# schematic.net
KiCad netlist of a schematic drawn in Altium Designer
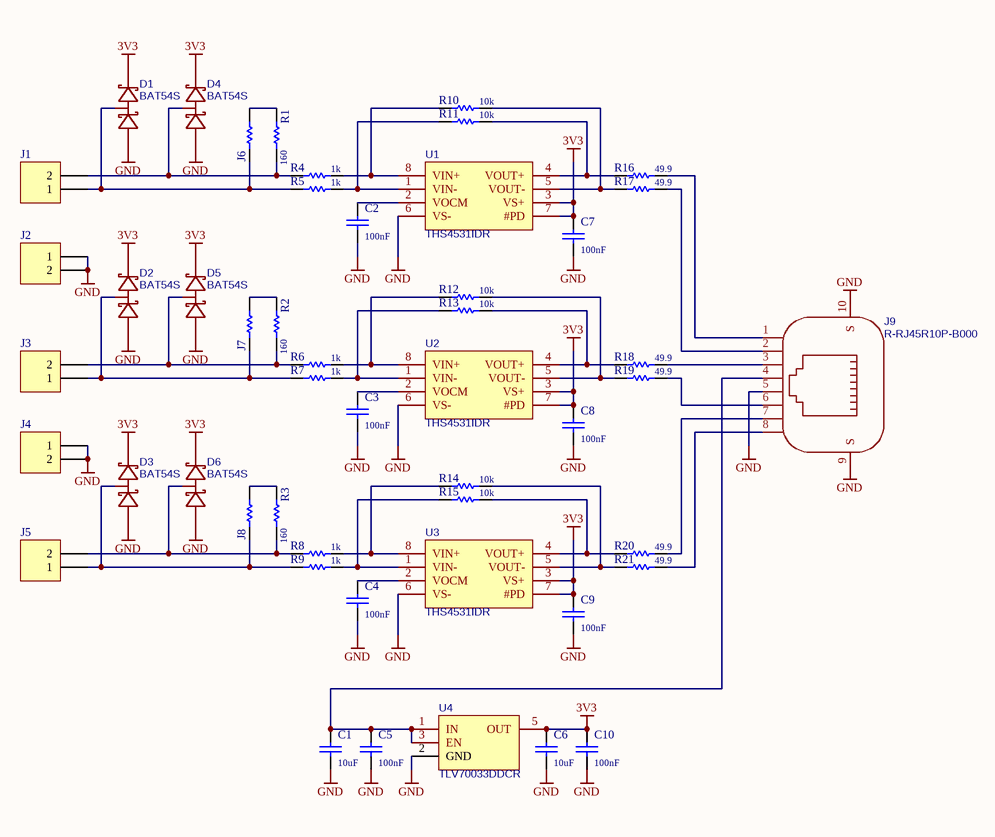
[diagram p0: schematic.SchDoc]

(export (version "E")
  (design (tool "Eeschema 10.0.6"))
  (components
    (comp (ref "C1")
      (value "10uF")
      (footprint "C0805")
      (description "10uf 50V 1206")
      (libsource (lib "Miscellaneous Devices") (part "CAP"))
    )
    (comp (ref "C2")
      (value "100nF")
      (footprint "C0603")
      (description "100nF 0603")
      (libsource (lib "Miscellaneous Devices") (part "CAP"))
    )
    (comp (ref "C3")
      (value "100nF")
      (footprint "C0603")
      (description "100nF 0603")
      (libsource (lib "Miscellaneous Devices") (part "CAP"))
    )
    (comp (ref "C4")
      (value "100nF")
      (footprint "C0603")
      (description "100nF 0603")
      (libsource (lib "Miscellaneous Devices") (part "CAP"))
    )
    (comp (ref "C5")
      (value "100nF")
      (footprint "C0603")
      (description "100nF 0603")
      (libsource (lib "Miscellaneous Devices") (part "CAP"))
    )
    (comp (ref "C6")
      (value "10uF")
      (footprint "C0805")
      (description "10uf 50V 1206")
      (libsource (lib "Miscellaneous Devices") (part "CAP"))
    )
    (comp (ref "C7")
      (value "100nF")
      (footprint "C0603")
      (description "100nF 0603")
      (libsource (lib "Miscellaneous Devices") (part "CAP"))
    )
    (comp (ref "C8")
      (value "100nF")
      (footprint "C0603")
      (description "100nF 0603")
      (libsource (lib "Miscellaneous Devices") (part "CAP"))
    )
    (comp (ref "C9")
      (value "100nF")
      (footprint "C0603")
      (description "100nF 0603")
      (libsource (lib "Miscellaneous Devices") (part "CAP"))
    )
    (comp (ref "C10")
      (value "100nF")
      (footprint "C0603")
      (description "100nF 0603")
      (libsource (lib "Miscellaneous Devices") (part "CAP"))
    )
    (comp (ref "D1")
      (value "BAT54S")
      (footprint "SOT-23")
      (libsource (lib "Schlib1") (part "BAT54S_C916425"))
    )
    (comp (ref "D2")
      (value "BAT54S")
      (footprint "SOT-23")
      (libsource (lib "Schlib1") (part "BAT54S_C916425"))
    )
    (comp (ref "D3")
      (value "BAT54S")
      (footprint "SOT-23")
      (libsource (lib "Schlib1") (part "BAT54S_C916425"))
    )
    (comp (ref "D4")
      (value "BAT54S")
      (footprint "SOT-23")
      (libsource (lib "Schlib1") (part "BAT54S_C916425"))
    )
    (comp (ref "D5")
      (value "BAT54S")
      (footprint "SOT-23")
      (libsource (lib "Schlib1") (part "BAT54S_C916425"))
    )
    (comp (ref "D6")
      (value "BAT54S")
      (footprint "SOT-23")
      (libsource (lib "Schlib1") (part "BAT54S_C916425"))
    )
    (comp (ref "J1")
      (value "DG308-2.54-02P-14-00A(H)")
      (footprint "CONN_DG308-2.54-2P")
      (libsource (lib "Miscellaneous Devices") (part "CONN MOLEX HDR-M 1x4"))
    )
    (comp (ref "J2")
      (value "DG308-2.54-02P-14-00A(H)")
      (footprint "CONN_DG308-2.54-2P")
      (libsource (lib "") (part "CONN MOLEX HDR-M 1x4_1"))
    )
    (comp (ref "J3")
      (value "DG308-2.54-02P-14-00A(H)")
      (footprint "CONN_DG308-2.54-2P")
      (libsource (lib "Miscellaneous Devices") (part "CONN MOLEX HDR-M 1x4"))
    )
    (comp (ref "J4")
      (value "DG308-2.54-02P-14-00A(H)")
      (footprint "CONN_DG308-2.54-2P")
      (libsource (lib "") (part "CONN MOLEX HDR-M 1x4_1"))
    )
    (comp (ref "J5")
      (value "DG308-2.54-02P-14-00A(H)")
      (footprint "CONN_DG308-2.54-2P")
      (libsource (lib "Miscellaneous Devices") (part "CONN MOLEX HDR-M 1x4"))
    )
    (comp (ref "J6")
      (value "undef")
      (footprint "R0603")
      (libsource (lib "Miscellaneous Devices") (part "RES"))
    )
    (comp (ref "J7")
      (value "undef")
      (footprint "R0603")
      (libsource (lib "Miscellaneous Devices") (part "RES"))
    )
    (comp (ref "J8")
      (value "undef")
      (footprint "R0603")
      (libsource (lib "Miscellaneous Devices") (part "RES"))
    )
    (comp (ref "J9")
      (value "R-RJ45R10P-B000")
      (footprint "RJ45-TH_R-RJ45R10P-B000")
      (libsource (lib "altium-import") (part "root_3_R-RJ45R10P-B000_"))
    )
    (comp (ref "R1")
      (value "160")
      (footprint "R0603")
      (description "160R 0603")
      (libsource (lib "Miscellaneous Devices") (part "RES"))
    )
    (comp (ref "R2")
      (value "160")
      (footprint "R0603")
      (description "160R 0603")
      (libsource (lib "Miscellaneous Devices") (part "RES"))
    )
    (comp (ref "R3")
      (value "160")
      (footprint "R0603")
      (description "160R 0603")
      (libsource (lib "Miscellaneous Devices") (part "RES"))
    )
    (comp (ref "R4")
      (value "1k")
      (footprint "R0603")
      (description "1k 0603")
      (libsource (lib "Miscellaneous Devices") (part "RES"))
    )
    (comp (ref "R5")
      (value "1k")
      (footprint "R0603")
      (description "1k 0603")
      (libsource (lib "Miscellaneous Devices") (part "RES"))
    )
    (comp (ref "R6")
      (value "1k")
      (footprint "R0603")
      (description "1k 0603")
      (libsource (lib "Miscellaneous Devices") (part "RES"))
    )
    (comp (ref "R7")
      (value "1k")
      (footprint "R0603")
      (description "1k 0603")
      (libsource (lib "Miscellaneous Devices") (part "RES"))
    )
    (comp (ref "R8")
      (value "1k")
      (footprint "R0603")
      (description "1k 0603")
      (libsource (lib "Miscellaneous Devices") (part "RES"))
    )
    (comp (ref "R9")
      (value "1k")
      (footprint "R0603")
      (description "1k 0603")
      (libsource (lib "Miscellaneous Devices") (part "RES"))
    )
    (comp (ref "R10")
      (value "10k")
      (footprint "R0603")
      (description "10k 0603")
      (libsource (lib "Miscellaneous Devices") (part "RES"))
    )
    (comp (ref "R11")
      (value "10k")
      (footprint "R0603")
      (description "10k 0603")
      (libsource (lib "Miscellaneous Devices") (part "RES"))
    )
    (comp (ref "R12")
      (value "10k")
      (footprint "R0603")
      (description "10k 0603")
      (libsource (lib "Miscellaneous Devices") (part "RES"))
    )
    (comp (ref "R13")
      (value "10k")
      (footprint "R0603")
      (description "10k 0603")
      (libsource (lib "Miscellaneous Devices") (part "RES"))
    )
    (comp (ref "R14")
      (value "10k")
      (footprint "R0603")
      (description "10k 0603")
      (libsource (lib "Miscellaneous Devices") (part "RES"))
    )
    (comp (ref "R15")
      (value "10k")
      (footprint "R0603")
      (description "10k 0603")
      (libsource (lib "Miscellaneous Devices") (part "RES"))
    )
    (comp (ref "R16")
      (value "49.9")
      (footprint "R0603")
      (description "49.9R")
      (libsource (lib "Miscellaneous Devices") (part "RES"))
    )
    (comp (ref "R17")
      (value "49.9")
      (footprint "R0603")
      (description "49.9R")
      (libsource (lib "Miscellaneous Devices") (part "RES"))
    )
    (comp (ref "R18")
      (value "49.9")
      (footprint "R0603")
      (description "49.9R")
      (libsource (lib "Miscellaneous Devices") (part "RES"))
    )
    (comp (ref "R19")
      (value "49.9")
      (footprint "R0603")
      (description "49.9R")
      (libsource (lib "Miscellaneous Devices") (part "RES"))
    )
    (comp (ref "R20")
      (value "49.9")
      (footprint "R0603")
      (description "49.9R")
      (libsource (lib "Miscellaneous Devices") (part "RES"))
    )
    (comp (ref "R21")
      (value "49.9")
      (footprint "R0603")
      (description "49.9R")
      (libsource (lib "Miscellaneous Devices") (part "RES"))
    )
    (comp (ref "U1") (value "THS4531IDR") (footprint "SO-8") (libsource (lib "Schlib1") (part "THS4531IDR")))
    (comp (ref "U2") (value "THS4531IDR") (footprint "SO-8") (libsource (lib "Schlib1") (part "THS4531IDR")))
    (comp (ref "U3") (value "THS4531IDR") (footprint "SO-8") (libsource (lib "Schlib1") (part "THS4531IDR")))
    (comp (ref "U4")
      (value "TLV70033DDCR")
      (footprint "SOT-23-5")
      (libsource (lib "Schlib1") (part "TLV70033DDCR"))
    )
  )
  (nets
    (net (code "1") (name "3V3") (class "Default")
      (node (ref "C10") (pin "2") (pinfunction "2_2") (pintype "passive"))
      (node (ref "C6") (pin "2") (pinfunction "2_2") (pintype "passive"))
      (node (ref "C7") (pin "2") (pinfunction "2_2") (pintype "passive"))
      (node (ref "C8") (pin "2") (pinfunction "2_2") (pintype "passive"))
      (node (ref "C9") (pin "2") (pinfunction "2_2") (pintype "passive"))
      (node (ref "D1") (pin "2") (pinfunction "K_2") (pintype "passive"))
      (node (ref "D2") (pin "2") (pinfunction "K_2") (pintype "passive"))
      (node (ref "D3") (pin "2") (pinfunction "K_2") (pintype "passive"))
      (node (ref "D4") (pin "2") (pinfunction "K_2") (pintype "passive"))
      (node (ref "D5") (pin "2") (pinfunction "K_2") (pintype "passive"))
      (node (ref "D6") (pin "2") (pinfunction "K_2") (pintype "passive"))
      (node (ref "U1") (pin "3") (pinfunction "VS+_3") (pintype "passive"))
      (node (ref "U1") (pin "7") (pinfunction "#PD_7") (pintype "passive"))
      (node (ref "U2") (pin "3") (pinfunction "VS+_3") (pintype "passive"))
      (node (ref "U2") (pin "7") (pinfunction "#PD_7") (pintype "passive"))
      (node (ref "U3") (pin "3") (pinfunction "VS+_3") (pintype "passive"))
      (node (ref "U3") (pin "7") (pinfunction "#PD_7") (pintype "passive"))
      (node (ref "U4") (pin "5") (pinfunction "OUT_5") (pintype "passive"))
    )
    (net (code "2") (name "GND") (class "Default")
      (node (ref "C1") (pin "1") (pinfunction "1_1") (pintype "passive"))
      (node (ref "C10") (pin "1") (pinfunction "1_1") (pintype "passive"))
      (node (ref "C2") (pin "1") (pinfunction "1_1") (pintype "passive"))
      (node (ref "C3") (pin "1") (pinfunction "1_1") (pintype "passive"))
      (node (ref "C4") (pin "1") (pinfunction "1_1") (pintype "passive"))
      (node (ref "C5") (pin "1") (pinfunction "1_1") (pintype "passive"))
      (node (ref "C6") (pin "1") (pinfunction "1_1") (pintype "passive"))
      (node (ref "C7") (pin "1") (pinfunction "1_1") (pintype "passive"))
      (node (ref "C8") (pin "1") (pinfunction "1_1") (pintype "passive"))
      (node (ref "C9") (pin "1") (pinfunction "1_1") (pintype "passive"))
      (node (ref "D1") (pin "1") (pinfunction "A_1") (pintype "passive"))
      (node (ref "D2") (pin "1") (pinfunction "A_1") (pintype "passive"))
      (node (ref "D3") (pin "1") (pinfunction "A_1") (pintype "passive"))
      (node (ref "D4") (pin "1") (pinfunction "A_1") (pintype "passive"))
      (node (ref "D5") (pin "1") (pinfunction "A_1") (pintype "passive"))
      (node (ref "D6") (pin "1") (pinfunction "A_1") (pintype "passive"))
      (node (ref "J2") (pin "1") (pinfunction "1_1") (pintype "passive"))
      (node (ref "J2") (pin "2") (pinfunction "2_2") (pintype "passive"))
      (node (ref "J4") (pin "1") (pinfunction "1_1") (pintype "passive"))
      (node (ref "J4") (pin "2") (pinfunction "2_2") (pintype "passive"))
      (node (ref "J9") (pin "10") (pinfunction "S_10") (pintype "passive"))
      (node (ref "J9") (pin "5") (pinfunction "5_5") (pintype "passive"))
      (node (ref "J9") (pin "9") (pinfunction "S_9") (pintype "passive"))
      (node (ref "U1") (pin "6") (pinfunction "VS-_6") (pintype "passive"))
      (node (ref "U2") (pin "6") (pinfunction "VS-_6") (pintype "passive"))
      (node (ref "U3") (pin "6") (pinfunction "VS-_6") (pintype "passive"))
      (node (ref "U4") (pin "2") (pinfunction "GND_2") (pintype "passive"))
    )
    (net (code "3") (name "Net-(D1-Pad3)") (class "Default")
      (node (ref "D1") (pin "3") (pinfunction "3_3") (pintype "passive"))
      (node (ref "J1") (pin "1") (pinfunction "1_1") (pintype "passive"))
      (node (ref "J6") (pin "1") (pinfunction "1_1") (pintype "passive"))
      (node (ref "R5") (pin "1") (pinfunction "1_1") (pintype "passive"))
    )
    (net (code "4") (name "Net-(D2-Pad3)") (class "Default")
      (node (ref "D2") (pin "3") (pinfunction "3_3") (pintype "passive"))
      (node (ref "J3") (pin "1") (pinfunction "1_1") (pintype "passive"))
      (node (ref "J7") (pin "1") (pinfunction "1_1") (pintype "passive"))
      (node (ref "R7") (pin "1") (pinfunction "1_1") (pintype "passive"))
    )
    (net (code "5") (name "Net-(D3-Pad3)") (class "Default")
      (node (ref "D3") (pin "3") (pinfunction "3_3") (pintype "passive"))
      (node (ref "J5") (pin "1") (pinfunction "1_1") (pintype "passive"))
      (node (ref "J8") (pin "1") (pinfunction "1_1") (pintype "passive"))
      (node (ref "R9") (pin "1") (pinfunction "1_1") (pintype "passive"))
    )
    (net (code "6") (name "Net-(D4-Pad3)") (class "Default")
      (node (ref "D4") (pin "3") (pinfunction "3_3") (pintype "passive"))
      (node (ref "J1") (pin "2") (pinfunction "2_2") (pintype "passive"))
      (node (ref "R1") (pin "2") (pinfunction "2_2") (pintype "passive"))
      (node (ref "R4") (pin "1") (pinfunction "1_1") (pintype "passive"))
    )
    (net (code "7") (name "Net-(D5-Pad3)") (class "Default")
      (node (ref "D5") (pin "3") (pinfunction "3_3") (pintype "passive"))
      (node (ref "J3") (pin "2") (pinfunction "2_2") (pintype "passive"))
      (node (ref "R2") (pin "2") (pinfunction "2_2") (pintype "passive"))
      (node (ref "R6") (pin "1") (pinfunction "1_1") (pintype "passive"))
    )
    (net (code "8") (name "Net-(D6-Pad3)") (class "Default")
      (node (ref "D6") (pin "3") (pinfunction "3_3") (pintype "passive"))
      (node (ref "J5") (pin "2") (pinfunction "2_2") (pintype "passive"))
      (node (ref "R3") (pin "2") (pinfunction "2_2") (pintype "passive"))
      (node (ref "R8") (pin "1") (pinfunction "1_1") (pintype "passive"))
    )
    (net (code "9") (name "Net-(J6-Pad2)") (class "Default")
      (node (ref "J6") (pin "2") (pinfunction "2_2") (pintype "passive"))
      (node (ref "R1") (pin "1") (pinfunction "1_1") (pintype "passive"))
    )
    (net (code "10") (name "Net-(J7-Pad2)") (class "Default")
      (node (ref "J7") (pin "2") (pinfunction "2_2") (pintype "passive"))
      (node (ref "R2") (pin "1") (pinfunction "1_1") (pintype "passive"))
    )
    (net (code "11") (name "Net-(J8-Pad2)") (class "Default")
      (node (ref "J8") (pin "2") (pinfunction "2_2") (pintype "passive"))
      (node (ref "R3") (pin "1") (pinfunction "1_1") (pintype "passive"))
    )
    (net (code "12") (name "Net-(J9-Pad1)") (class "Default")
      (node (ref "J9") (pin "1") (pinfunction "1_1") (pintype "passive"))
      (node (ref "R16") (pin "2") (pinfunction "2_2") (pintype "passive"))
    )
    (net (code "13") (name "Net-(J9-Pad2)") (class "Default")
      (node (ref "J9") (pin "2") (pinfunction "2_2") (pintype "passive"))
      (node (ref "R17") (pin "2") (pinfunction "2_2") (pintype "passive"))
    )
    (net (code "14") (name "Net-(J9-Pad3)") (class "Default")
      (node (ref "J9") (pin "3") (pinfunction "3_3") (pintype "passive"))
      (node (ref "R18") (pin "2") (pinfunction "2_2") (pintype "passive"))
    )
    (net (code "15") (name "Net-(J9-Pad6)") (class "Default")
      (node (ref "J9") (pin "6") (pinfunction "6_6") (pintype "passive"))
      (node (ref "R19") (pin "2") (pinfunction "2_2") (pintype "passive"))
    )
    (net (code "16") (name "Net-(J9-Pad7)") (class "Default")
      (node (ref "J9") (pin "7") (pinfunction "7_7") (pintype "passive"))
      (node (ref "R20") (pin "2") (pinfunction "2_2") (pintype "passive"))
    )
    (net (code "17") (name "Net-(J9-Pad8)") (class "Default")
      (node (ref "J9") (pin "8") (pinfunction "8_8") (pintype "passive"))
      (node (ref "R21") (pin "2") (pinfunction "2_2") (pintype "passive"))
    )
    (net (code "18") (name "Net-(U1-VIN+)") (class "Default")
      (node (ref "R10") (pin "1") (pinfunction "1_1") (pintype "passive"))
      (node (ref "R4") (pin "2") (pinfunction "2_2") (pintype "passive"))
      (node (ref "U1") (pin "8") (pinfunction "VIN+_8") (pintype "passive"))
    )
    (net (code "19") (name "Net-(U1-VIN-)") (class "Default")
      (node (ref "R11") (pin "1") (pinfunction "1_1") (pintype "passive"))
      (node (ref "R5") (pin "2") (pinfunction "2_2") (pintype "passive"))
      (node (ref "U1") (pin "1") (pinfunction "VIN-_1") (pintype "passive"))
    )
    (net (code "20") (name "Net-(U1-VOCM)") (class "Default")
      (node (ref "C2") (pin "2") (pinfunction "2_2") (pintype "passive"))
      (node (ref "U1") (pin "2") (pinfunction "VOCM_2") (pintype "passive"))
    )
    (net (code "21") (name "Net-(U1-VOUT+)") (class "Default")
      (node (ref "R11") (pin "2") (pinfunction "2_2") (pintype "passive"))
      (node (ref "R16") (pin "1") (pinfunction "1_1") (pintype "passive"))
      (node (ref "U1") (pin "4") (pinfunction "VOUT+_4") (pintype "passive"))
    )
    (net (code "22") (name "Net-(U1-VOUT-)") (class "Default")
      (node (ref "R10") (pin "2") (pinfunction "2_2") (pintype "passive"))
      (node (ref "R17") (pin "1") (pinfunction "1_1") (pintype "passive"))
      (node (ref "U1") (pin "5") (pinfunction "VOUT-_5") (pintype "passive"))
    )
    (net (code "23") (name "Net-(U2-VIN+)") (class "Default")
      (node (ref "R12") (pin "1") (pinfunction "1_1") (pintype "passive"))
      (node (ref "R6") (pin "2") (pinfunction "2_2") (pintype "passive"))
      (node (ref "U2") (pin "8") (pinfunction "VIN+_8") (pintype "passive"))
    )
    (net (code "24") (name "Net-(U2-VIN-)") (class "Default")
      (node (ref "R13") (pin "1") (pinfunction "1_1") (pintype "passive"))
      (node (ref "R7") (pin "2") (pinfunction "2_2") (pintype "passive"))
      (node (ref "U2") (pin "1") (pinfunction "VIN-_1") (pintype "passive"))
    )
    (net (code "25") (name "Net-(U2-VOCM)") (class "Default")
      (node (ref "C3") (pin "2") (pinfunction "2_2") (pintype "passive"))
      (node (ref "U2") (pin "2") (pinfunction "VOCM_2") (pintype "passive"))
    )
    (net (code "26") (name "Net-(U2-VOUT+)") (class "Default")
      (node (ref "R13") (pin "2") (pinfunction "2_2") (pintype "passive"))
      (node (ref "R18") (pin "1") (pinfunction "1_1") (pintype "passive"))
      (node (ref "U2") (pin "4") (pinfunction "VOUT+_4") (pintype "passive"))
    )
    (net (code "27") (name "Net-(U2-VOUT-)") (class "Default")
      (node (ref "R12") (pin "2") (pinfunction "2_2") (pintype "passive"))
      (node (ref "R19") (pin "1") (pinfunction "1_1") (pintype "passive"))
      (node (ref "U2") (pin "5") (pinfunction "VOUT-_5") (pintype "passive"))
    )
    (net (code "28") (name "Net-(U3-VIN+)") (class "Default")
      (node (ref "R14") (pin "1") (pinfunction "1_1") (pintype "passive"))
      (node (ref "R8") (pin "2") (pinfunction "2_2") (pintype "passive"))
      (node (ref "U3") (pin "8") (pinfunction "VIN+_8") (pintype "passive"))
    )
    (net (code "29") (name "Net-(U3-VIN-)") (class "Default")
      (node (ref "R15") (pin "1") (pinfunction "1_1") (pintype "passive"))
      (node (ref "R9") (pin "2") (pinfunction "2_2") (pintype "passive"))
      (node (ref "U3") (pin "1") (pinfunction "VIN-_1") (pintype "passive"))
    )
    (net (code "30") (name "Net-(U3-VOCM)") (class "Default")
      (node (ref "C4") (pin "2") (pinfunction "2_2") (pintype "passive"))
      (node (ref "U3") (pin "2") (pinfunction "VOCM_2") (pintype "passive"))
    )
    (net (code "31") (name "Net-(U3-VOUT+)") (class "Default")
      (node (ref "R15") (pin "2") (pinfunction "2_2") (pintype "passive"))
      (node (ref "R20") (pin "1") (pinfunction "1_1") (pintype "passive"))
      (node (ref "U3") (pin "4") (pinfunction "VOUT+_4") (pintype "passive"))
    )
    (net (code "32") (name "Net-(U3-VOUT-)") (class "Default")
      (node (ref "R14") (pin "2") (pinfunction "2_2") (pintype "passive"))
      (node (ref "R21") (pin "1") (pinfunction "1_1") (pintype "passive"))
      (node (ref "U3") (pin "5") (pinfunction "VOUT-_5") (pintype "passive"))
    )
    (net (code "33") (name "Net-(U4-EN)") (class "Default")
      (node (ref "C1") (pin "2") (pinfunction "2_2") (pintype "passive"))
      (node (ref "C5") (pin "2") (pinfunction "2_2") (pintype "passive"))
      (node (ref "J9") (pin "4") (pinfunction "4_4") (pintype "passive"))
      (node (ref "U4") (pin "1") (pinfunction "IN_1") (pintype "passive"))
      (node (ref "U4") (pin "3") (pinfunction "EN_3") (pintype "passive"))
    )
  )
)
